# 01_MAIN.net
KiCad netlist of a schematic drawn in Altium Designer
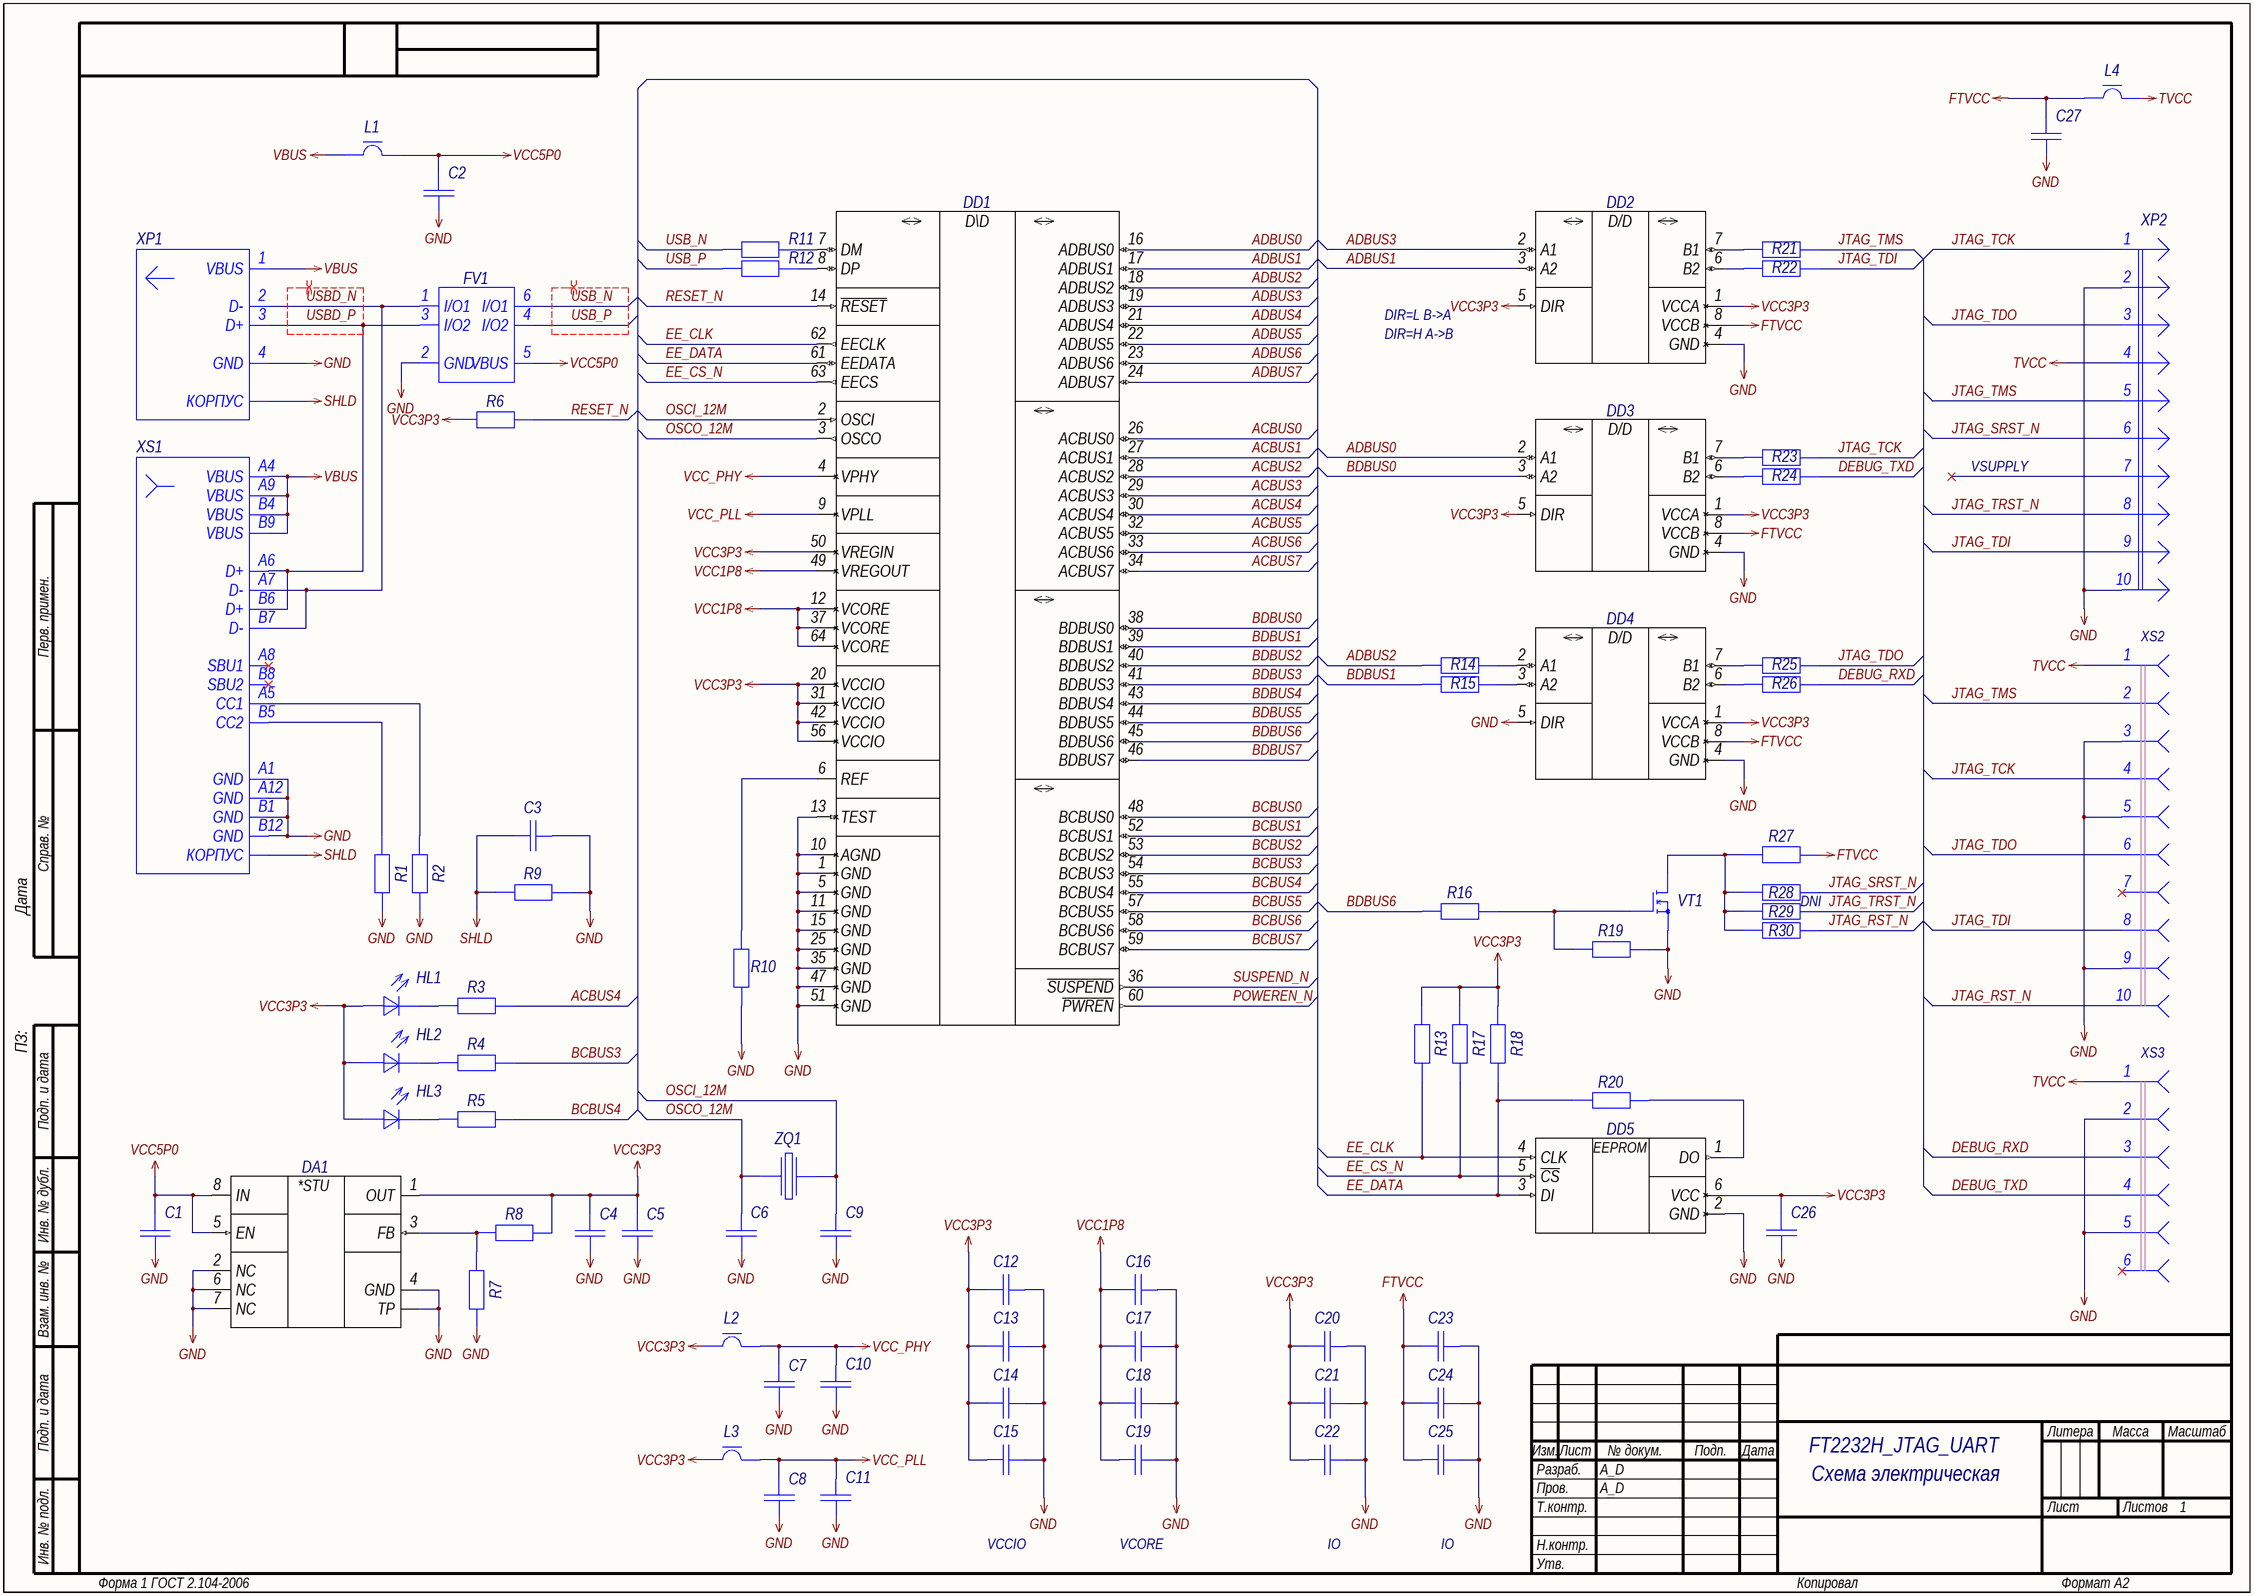
[diagram p0: 01_MAIN.SchDoc]

(export (version "E")
  (design (tool "Eeschema 10.0.6"))
  (components
    (comp (ref "C1")
      (value "Capacitor")
      (footprint "C0402_L")
      (fields
        (field (name "PART NUMBER") "GRM155R61C105KA12D")
        (field (name "VOLTAGE") "16V")
        (field (name "TOLERANCE") "±10%")
        (field (name "PUBLISHER") "Andrew Danich")
      )
      (libsource (lib "ADLib") (part "Capacitor"))
    )
    (comp (ref "C2")
      (value "Capacitor")
      (footprint "C0603_L")
      (fields
        (field (name "PART NUMBER") "GRM188R61A106KE69D")
        (field (name "VOLTAGE") "10V")
        (field (name "TOLERANCE") "±10%")
        (field (name "PUBLISHER") "Andrew Danich")
      )
      (libsource (lib "ADLib") (part "Capacitor"))
    )
    (comp (ref "C3")
      (value "~")
      (footprint "C0402_L")
      (fields
        (field (name "PART NUMBER") "GCM155R71C104KA55D")
        (field (name "VOLTAGE") "16V")
        (field (name "TOLERANCE") "±10%")
        (field (name "PUBLISHER") "Andrew Danich")
      )
      (libsource (lib "ADLib") (part "Capacitor"))
    )
    (comp (ref "C4")
      (value "Capacitor")
      (footprint "C0402_L")
      (fields
        (field (name "PART NUMBER") "GRM155R60J475ME87D")
        (field (name "VOLTAGE") "6.3V")
        (field (name "TOLERANCE") "±20%")
        (field (name "PUBLISHER") "Andrew Danich")
      )
      (libsource (lib "ADLib") (part "Capacitor"))
    )
    (comp (ref "C5")
      (value "Capacitor")
      (footprint "C0402_L")
      (fields
        (field (name "PART NUMBER") "GRM155R60J475ME87D")
        (field (name "VOLTAGE") "6.3V")
        (field (name "TOLERANCE") "±20%")
        (field (name "PUBLISHER") "Andrew Danich")
      )
      (libsource (lib "ADLib") (part "Capacitor"))
    )
    (comp (ref "C6")
      (value "Capacitor")
      (footprint "C0402_L")
      (fields
        (field (name "PART NUMBER") "GJM1555C1H120GB01D")
        (field (name "VOLTAGE") "50V")
        (field (name "TOLERANCE") "±2%")
        (field (name "PUBLISHER") "Andrew Danich")
      )
      (libsource (lib "ADLib") (part "Capacitor"))
    )
    (comp (ref "C7")
      (value "Capacitor")
      (footprint "C0402_L")
      (fields
        (field (name "PART NUMBER") "GRM155R60J475ME87D")
        (field (name "VOLTAGE") "6.3V")
        (field (name "TOLERANCE") "±20%")
        (field (name "PUBLISHER") "Andrew Danich")
      )
      (libsource (lib "ADLib") (part "Capacitor"))
    )
    (comp (ref "C8")
      (value "Capacitor")
      (footprint "C0402_L")
      (fields
        (field (name "PART NUMBER") "GRM155R60J475ME87D")
        (field (name "VOLTAGE") "6.3V")
        (field (name "TOLERANCE") "±20%")
        (field (name "PUBLISHER") "Andrew Danich")
      )
      (libsource (lib "ADLib") (part "Capacitor"))
    )
    (comp (ref "C9")
      (value "Capacitor")
      (footprint "C0402_L")
      (fields
        (field (name "PART NUMBER") "GJM1555C1H120GB01D")
        (field (name "VOLTAGE") "50V")
        (field (name "TOLERANCE") "±2%")
        (field (name "PUBLISHER") "Andrew Danich")
      )
      (libsource (lib "ADLib") (part "Capacitor"))
    )
    (comp (ref "C10")
      (value "Capacitor")
      (footprint "C0402_L")
      (fields
        (field (name "PART NUMBER") "GCM155R71C104KA55D")
        (field (name "VOLTAGE") "16V")
        (field (name "TOLERANCE") "±10%")
        (field (name "PUBLISHER") "Andrew Danich")
      )
      (libsource (lib "ADLib") (part "Capacitor"))
    )
    (comp (ref "C11")
      (value "Capacitor")
      (footprint "C0402_L")
      (fields
        (field (name "PART NUMBER") "GCM155R71C104KA55D")
        (field (name "VOLTAGE") "16V")
        (field (name "TOLERANCE") "±10%")
        (field (name "PUBLISHER") "Andrew Danich")
      )
      (libsource (lib "ADLib") (part "Capacitor"))
    )
    (comp (ref "C12")
      (value "Capacitor")
      (footprint "C0402_L")
      (fields
        (field (name "PART NUMBER") "GCM155R71C104KA55D")
        (field (name "VOLTAGE") "16V")
        (field (name "TOLERANCE") "±10%")
        (field (name "PUBLISHER") "Andrew Danich")
      )
      (libsource (lib "ADLib") (part "Capacitor"))
    )
    (comp (ref "C13")
      (value "Capacitor")
      (footprint "C0402_L")
      (fields
        (field (name "PART NUMBER") "GCM155R71C104KA55D")
        (field (name "VOLTAGE") "16V")
        (field (name "TOLERANCE") "±10%")
        (field (name "PUBLISHER") "Andrew Danich")
      )
      (libsource (lib "ADLib") (part "Capacitor"))
    )
    (comp (ref "C14")
      (value "Capacitor")
      (footprint "C0402_L")
      (fields
        (field (name "PART NUMBER") "GCM155R71C104KA55D")
        (field (name "VOLTAGE") "16V")
        (field (name "TOLERANCE") "±10%")
        (field (name "PUBLISHER") "Andrew Danich")
      )
      (libsource (lib "ADLib") (part "Capacitor"))
    )
    (comp (ref "C15")
      (value "Capacitor")
      (footprint "C0402_L")
      (fields
        (field (name "PART NUMBER") "GCM155R71C104KA55D")
        (field (name "VOLTAGE") "16V")
        (field (name "TOLERANCE") "±10%")
        (field (name "PUBLISHER") "Andrew Danich")
      )
      (libsource (lib "ADLib") (part "Capacitor"))
    )
    (comp (ref "C16")
      (value "Capacitor")
      (footprint "C0402_L")
      (fields
        (field (name "PART NUMBER") "GRM155R60J475ME87D")
        (field (name "VOLTAGE") "6.3V")
        (field (name "TOLERANCE") "±20%")
        (field (name "PUBLISHER") "Andrew Danich")
      )
      (libsource (lib "ADLib") (part "Capacitor"))
    )
    (comp (ref "C17")
      (value "Capacitor")
      (footprint "C0402_L")
      (fields
        (field (name "PART NUMBER") "GCM155R71C104KA55D")
        (field (name "VOLTAGE") "16V")
        (field (name "TOLERANCE") "±10%")
        (field (name "PUBLISHER") "Andrew Danich")
      )
      (libsource (lib "ADLib") (part "Capacitor"))
    )
    (comp (ref "C18")
      (value "Capacitor")
      (footprint "C0402_L")
      (fields
        (field (name "PART NUMBER") "GCM155R71C104KA55D")
        (field (name "VOLTAGE") "16V")
        (field (name "TOLERANCE") "±10%")
        (field (name "PUBLISHER") "Andrew Danich")
      )
      (libsource (lib "ADLib") (part "Capacitor"))
    )
    (comp (ref "C19")
      (value "Capacitor")
      (footprint "C0402_L")
      (fields
        (field (name "PART NUMBER") "GCM155R71C104KA55D")
        (field (name "VOLTAGE") "16V")
        (field (name "TOLERANCE") "±10%")
        (field (name "PUBLISHER") "Andrew Danich")
      )
      (libsource (lib "ADLib") (part "Capacitor"))
    )
    (comp (ref "C20")
      (value "Capacitor")
      (footprint "C0402_L")
      (fields
        (field (name "PART NUMBER") "GCM155R71C104KA55D")
        (field (name "VOLTAGE") "16V")
        (field (name "TOLERANCE") "±10%")
        (field (name "PUBLISHER") "Andrew Danich")
      )
      (libsource (lib "ADLib") (part "Capacitor"))
    )
    (comp (ref "C21")
      (value "Capacitor")
      (footprint "C0402_L")
      (fields
        (field (name "PART NUMBER") "GCM155R71C104KA55D")
        (field (name "VOLTAGE") "16V")
        (field (name "TOLERANCE") "±10%")
        (field (name "PUBLISHER") "Andrew Danich")
      )
      (libsource (lib "ADLib") (part "Capacitor"))
    )
    (comp (ref "C22")
      (value "Capacitor")
      (footprint "C0402_L")
      (fields
        (field (name "PART NUMBER") "GCM155R71C104KA55D")
        (field (name "VOLTAGE") "16V")
        (field (name "TOLERANCE") "±10%")
        (field (name "PUBLISHER") "Andrew Danich")
      )
      (libsource (lib "ADLib") (part "Capacitor"))
    )
    (comp (ref "C23")
      (value "Capacitor")
      (footprint "C0402_L")
      (fields
        (field (name "PART NUMBER") "GCM155R71C104KA55D")
        (field (name "VOLTAGE") "16V")
        (field (name "TOLERANCE") "±10%")
        (field (name "PUBLISHER") "Andrew Danich")
      )
      (libsource (lib "ADLib") (part "Capacitor"))
    )
    (comp (ref "C24")
      (value "Capacitor")
      (footprint "C0402_L")
      (fields
        (field (name "PART NUMBER") "GCM155R71C104KA55D")
        (field (name "VOLTAGE") "16V")
        (field (name "TOLERANCE") "±10%")
        (field (name "PUBLISHER") "Andrew Danich")
      )
      (libsource (lib "ADLib") (part "Capacitor"))
    )
    (comp (ref "C25")
      (value "Capacitor")
      (footprint "C0402_L")
      (fields
        (field (name "PART NUMBER") "GCM155R71C104KA55D")
        (field (name "VOLTAGE") "16V")
        (field (name "TOLERANCE") "±10%")
        (field (name "PUBLISHER") "Andrew Danich")
      )
      (libsource (lib "ADLib") (part "Capacitor"))
    )
    (comp (ref "C26")
      (value "Capacitor")
      (footprint "C0402_L")
      (fields
        (field (name "PART NUMBER") "GCM155R71C104KA55D")
        (field (name "VOLTAGE") "16V")
        (field (name "TOLERANCE") "±10%")
        (field (name "PUBLISHER") "Andrew Danich")
      )
      (libsource (lib "ADLib") (part "Capacitor"))
    )
    (comp (ref "C27")
      (value "Capacitor")
      (footprint "C0402_L")
      (fields
        (field (name "PART NUMBER") "GRM155D71C225ME11D")
        (field (name "VOLTAGE") "16V")
        (field (name "TOLERANCE") "±20%")
        (field (name "PUBLISHER") "Andrew Danich")
      )
      (libsource (lib "ADLib") (part "Capacitor"))
    )
    (comp (ref "DA1")
      (value "TPS73701DRB")
      (footprint "VSON-8_065P300X300X100_N")
      (fields
        (field (name "PART NUMBER") "TPS73701DRBR")
        (field (name "MANUFACTURER") "Texas Instruments")
        (field (name "PUBLISHER") "Andrew Danich")
      )
      (libsource (lib "ADLib") (part "TPS73701DRB"))
    )
    (comp (ref "DD1")
      (value "FT2232Hx-Series")
      (footprint "LQFP-64_050P1000X1000X160_N")
      (fields
        (field (name "PART NUMBER") "FT2232HL")
        (field (name "MANUFACTURER") "FTDI")
        (field (name "PUBLISHER") "Andrew Danich")
      )
      (libsource (lib "ADLib") (part "FT2232Hx-Series"))
    )
    (comp (ref "DD2")
      (value "SN74LVC2T45DCx-Series")
      (footprint "VSSOP-8_050P200X230X090_N")
      (fields
        (field (name "PART NUMBER") "SN74LVC2T45DCUR")
        (field (name "MANUFACTURER") "Texas Instruments")
        (field (name "PUBLISHER") "Andrew Danich")
      )
      (libsource (lib "ADLib") (part "SN74LVC2T45DCx-Series"))
    )
    (comp (ref "DD3")
      (value "SN74LVC2T45DCx-Series")
      (footprint "VSSOP-8_050P200X230X090_N")
      (fields
        (field (name "PART NUMBER") "SN74LVC2T45DCUR")
        (field (name "MANUFACTURER") "Texas Instruments")
        (field (name "PUBLISHER") "Andrew Danich")
      )
      (libsource (lib "ADLib") (part "SN74LVC2T45DCx-Series"))
    )
    (comp (ref "DD4")
      (value "SN74LVC2T45DCx-Series")
      (footprint "VSSOP-8_050P200X230X090_N")
      (fields
        (field (name "PART NUMBER") "SN74LVC2T45DCUR")
        (field (name "MANUFACTURER") "Texas Instruments")
        (field (name "PUBLISHER") "Andrew Danich")
      )
      (libsource (lib "ADLib") (part "SN74LVC2T45DCx-Series"))
    )
    (comp (ref "DD5")
      (value "93xx56xx-OT-Series")
      (footprint "SOT-23-6_095P290X160X145_N")
      (fields
        (field (name "PART NUMBER") "93LC56BT-I/OT")
        (field (name "MANUFACTURER") "Microchip")
        (field (name "PUBLISHER") "Andrew Danich")
      )
      (libsource (lib "ADLib") (part "93xx56xx-OT-Series"))
    )
    (comp (ref "FV1")
      (value "USBLC6-2x6")
      (footprint "SOT-666_050P160X120X060_N")
      (fields
        (field (name "PART NUMBER") "USBLC6-2P6")
        (field (name "MANUFACTURER") "STMicroelectronics")
        (field (name "PUBLISHER") "Andrew Danich")
      )
      (libsource (lib "ADLib") (part "USBLC6-2x6"))
    )
    (comp (ref "HL1")
      (value "Text")
      (footprint "LD0402")
      (fields
        (field (name "PART NUMBER") "KPHHS-1005QBC-D-V")
        (field (name "MANUFACTURER") "Kingbright")
        (field (name "PUBLISHER") "Andrew Danich")
      )
      (libsource (lib "ADLib") (part "Led-1"))
    )
    (comp (ref "HL2")
      (value "Text")
      (footprint "LD0402")
      (fields
        (field (name "PART NUMBER") "KPHHS-1005QBC-D-V")
        (field (name "MANUFACTURER") "Kingbright")
        (field (name "PUBLISHER") "Andrew Danich")
      )
      (libsource (lib "ADLib") (part "Led-1"))
    )
    (comp (ref "HL3")
      (value "Text")
      (footprint "LD0402")
      (fields
        (field (name "PART NUMBER") "KPHHS-1005QBC-D-V")
        (field (name "MANUFACTURER") "Kingbright")
        (field (name "PUBLISHER") "Andrew Danich")
      )
      (libsource (lib "ADLib") (part "Led-1"))
    )
    (comp (ref "L1")
      (value "FerriteBead")
      (footprint "L0402_L")
      (fields
        (field (name "PART NUMBER") "BLM15PD121SN1D")
        (field (name "TOLERANCE") "±25%")
        (field (name "MANUFACTURER") "Murata")
        (field (name "PUBLISHER") "Andrew Danich")
      )
      (libsource (lib "ADLib") (part "FerriteBead"))
    )
    (comp (ref "L2")
      (value "FerriteBead")
      (footprint "L0402_L")
      (fields
        (field (name "PART NUMBER") "BLM15PD121SN1D")
        (field (name "TOLERANCE") "±25%")
        (field (name "MANUFACTURER") "Murata")
        (field (name "PUBLISHER") "Andrew Danich")
      )
      (libsource (lib "ADLib") (part "FerriteBead"))
    )
    (comp (ref "L3")
      (value "FerriteBead")
      (footprint "L0402_L")
      (fields
        (field (name "PART NUMBER") "BLM15PD121SN1D")
        (field (name "TOLERANCE") "±25%")
        (field (name "MANUFACTURER") "Murata")
        (field (name "PUBLISHER") "Andrew Danich")
      )
      (libsource (lib "ADLib") (part "FerriteBead"))
    )
    (comp (ref "L4")
      (value "FerriteBead")
      (footprint "L0402_L")
      (fields
        (field (name "PART NUMBER") "BLM15PD121SN1D")
        (field (name "TOLERANCE") "±25%")
        (field (name "MANUFACTURER") "Murata")
        (field (name "PUBLISHER") "Andrew Danich")
      )
      (libsource (lib "ADLib") (part "FerriteBead"))
    )
    (comp (ref "R1")
      (value "Resistor")
      (footprint "R0402_L")
      (fields
        (field (name "PART NUMBER") "RC0402FR-075K1L")
        (field (name "TOLERANCE") "±1%")
        (field (name "MANUFACTURER") "Yageo")
        (field (name "PUBLISHER") "Andrew Danich")
      )
      (libsource (lib "ADLib") (part "Resistor"))
    )
    (comp (ref "R2")
      (value "Resistor")
      (footprint "R0402_L")
      (fields
        (field (name "PART NUMBER") "RC0402FR-075K1L")
        (field (name "TOLERANCE") "±1%")
        (field (name "MANUFACTURER") "Yageo")
        (field (name "PUBLISHER") "Andrew Danich")
      )
      (libsource (lib "ADLib") (part "Resistor"))
    )
    (comp (ref "R3")
      (value "Resistor")
      (footprint "R0402_L")
      (fields
        (field (name "PART NUMBER") "RC0402JR-071KL")
        (field (name "TOLERANCE") "±5%")
        (field (name "MANUFACTURER") "Yageo")
        (field (name "PUBLISHER") "Andrew Danich")
      )
      (libsource (lib "ADLib") (part "Resistor"))
    )
    (comp (ref "R4")
      (value "Resistor")
      (footprint "R0402_L")
      (fields
        (field (name "PART NUMBER") "RC0402JR-071KL")
        (field (name "TOLERANCE") "±5%")
        (field (name "MANUFACTURER") "Yageo")
        (field (name "PUBLISHER") "Andrew Danich")
      )
      (libsource (lib "ADLib") (part "Resistor"))
    )
    (comp (ref "R5")
      (value "Resistor")
      (footprint "R0402_L")
      (fields
        (field (name "PART NUMBER") "RC0402JR-071KL")
        (field (name "TOLERANCE") "±5%")
        (field (name "MANUFACTURER") "Yageo")
        (field (name "PUBLISHER") "Andrew Danich")
      )
      (libsource (lib "ADLib") (part "Resistor"))
    )
    (comp (ref "R6")
      (value "Resistor")
      (footprint "R0402_L")
      (fields
        (field (name "PART NUMBER") "RC0402JR-071KL")
        (field (name "TOLERANCE") "±5%")
        (field (name "MANUFACTURER") "Yageo")
        (field (name "PUBLISHER") "Andrew Danich")
      )
      (libsource (lib "ADLib") (part "Resistor"))
    )
    (comp (ref "R7")
      (value "Resistor")
      (footprint "R0402_L")
      (fields
        (field (name "PART NUMBER") "RC0402FR-0712KL")
        (field (name "TOLERANCE") "±1%")
        (field (name "MANUFACTURER") "Yageo")
        (field (name "PUBLISHER") "Andrew Danich")
      )
      (libsource (lib "ADLib") (part "Resistor"))
    )
    (comp (ref "R8")
      (value "Resistor")
      (footprint "R0402_L")
      (fields
        (field (name "PART NUMBER") "RC0402FR-0722K1L")
        (field (name "TOLERANCE") "±1%")
        (field (name "MANUFACTURER") "Yageo")
        (field (name "PUBLISHER") "Andrew Danich")
      )
      (libsource (lib "ADLib") (part "Resistor"))
    )
    (comp (ref "R9")
      (value "~")
      (footprint "R0402_L")
      (fields
        (field (name "PART NUMBER") "RC0402JR-07100KL")
        (field (name "TOLERANCE") "±5%")
        (field (name "MANUFACTURER") "Yageo")
        (field (name "PUBLISHER") "Andrew Danich")
      )
      (libsource (lib "ADLib") (part "Resistor"))
    )
    (comp (ref "R10")
      (value "Resistor")
      (footprint "R0402_L")
      (fields
        (field (name "PART NUMBER") "RC0402FR-0712KL")
        (field (name "TOLERANCE") "±1%")
        (field (name "MANUFACTURER") "Yageo")
        (field (name "PUBLISHER") "Andrew Danich")
      )
      (libsource (lib "ADLib") (part "Resistor"))
    )
    (comp (ref "R11")
      (value "Resistor")
      (footprint "R0402_L")
      (fields
        (field (name "PART NUMBER") "RC0402JR-0710RL")
        (field (name "TOLERANCE") "±5%")
        (field (name "MANUFACTURER") "Yageo")
        (field (name "PUBLISHER") "Andrew Danich")
      )
      (libsource (lib "ADLib") (part "Resistor"))
    )
    (comp (ref "R12")
      (value "Resistor")
      (footprint "R0402_L")
      (fields
        (field (name "PART NUMBER") "RC0402JR-0710RL")
        (field (name "TOLERANCE") "±5%")
        (field (name "MANUFACTURER") "Yageo")
        (field (name "PUBLISHER") "Andrew Danich")
      )
      (libsource (lib "ADLib") (part "Resistor"))
    )
    (comp (ref "R13")
      (value "Resistor")
      (footprint "R0402_L")
      (fields
        (field (name "PART NUMBER") "RC0402JR-0710KL")
        (field (name "TOLERANCE") "±5%")
        (field (name "MANUFACTURER") "Yageo")
        (field (name "PUBLISHER") "Andrew Danich")
      )
      (libsource (lib "ADLib") (part "Resistor"))
    )
    (comp (ref "R14")
      (value "Resistor")
      (footprint "R0402_L")
      (fields
        (field (name "PART NUMBER") "RC0402JR-07100RL")
        (field (name "TOLERANCE") "±5%")
        (field (name "MANUFACTURER") "Yageo")
        (field (name "PUBLISHER") "Andrew Danich")
      )
      (libsource (lib "ADLib") (part "Resistor"))
    )
    (comp (ref "R15")
      (value "Resistor")
      (footprint "R0402_L")
      (fields
        (field (name "PART NUMBER") "RC0402JR-07100RL")
        (field (name "TOLERANCE") "±5%")
        (field (name "MANUFACTURER") "Yageo")
        (field (name "PUBLISHER") "Andrew Danich")
      )
      (libsource (lib "ADLib") (part "Resistor"))
    )
    (comp (ref "R16")
      (value "Resistor")
      (footprint "R0402_L")
      (fields
        (field (name "PART NUMBER") "RC0402JR-07100RL")
        (field (name "TOLERANCE") "±5%")
        (field (name "MANUFACTURER") "Yageo")
        (field (name "PUBLISHER") "Andrew Danich")
      )
      (libsource (lib "ADLib") (part "Resistor"))
    )
    (comp (ref "R17")
      (value "Resistor")
      (footprint "R0402_L")
      (fields
        (field (name "PART NUMBER") "RC0402JR-0710KL")
        (field (name "TOLERANCE") "±5%")
        (field (name "MANUFACTURER") "Yageo")
        (field (name "PUBLISHER") "Andrew Danich")
      )
      (libsource (lib "ADLib") (part "Resistor"))
    )
    (comp (ref "R18")
      (value "Resistor")
      (footprint "R0402_L")
      (fields
        (field (name "PART NUMBER") "RC0402JR-0710KL")
        (field (name "TOLERANCE") "±5%")
        (field (name "MANUFACTURER") "Yageo")
        (field (name "PUBLISHER") "Andrew Danich")
      )
      (libsource (lib "ADLib") (part "Resistor"))
    )
    (comp (ref "R19")
      (value "Resistor")
      (footprint "R0402_L")
      (fields
        (field (name "PART NUMBER") "RC0402JR-0710KL")
        (field (name "TOLERANCE") "±5%")
        (field (name "MANUFACTURER") "Yageo")
        (field (name "PUBLISHER") "Andrew Danich")
      )
      (libsource (lib "ADLib") (part "Resistor"))
    )
    (comp (ref "R20")
      (value "Resistor")
      (footprint "R0402_L")
      (fields
        (field (name "PART NUMBER") "RC0402JR-072K2L")
        (field (name "TOLERANCE") "±5%")
        (field (name "MANUFACTURER") "Yageo")
        (field (name "PUBLISHER") "Andrew Danich")
      )
      (libsource (lib "ADLib") (part "Resistor"))
    )
    (comp (ref "R21")
      (value "Resistor")
      (footprint "R0402_L")
      (fields
        (field (name "PART NUMBER") "RC0402JR-07100RL")
        (field (name "TOLERANCE") "±5%")
        (field (name "MANUFACTURER") "Yageo")
        (field (name "PUBLISHER") "Andrew Danich")
      )
      (libsource (lib "ADLib") (part "Resistor"))
    )
    (comp (ref "R22")
      (value "Resistor")
      (footprint "R0402_L")
      (fields
        (field (name "PART NUMBER") "RC0402JR-07100RL")
        (field (name "TOLERANCE") "±5%")
        (field (name "MANUFACTURER") "Yageo")
        (field (name "PUBLISHER") "Andrew Danich")
      )
      (libsource (lib "ADLib") (part "Resistor"))
    )
    (comp (ref "R23")
      (value "Resistor")
      (footprint "R0402_L")
      (fields
        (field (name "PART NUMBER") "RC0402JR-07100RL")
        (field (name "TOLERANCE") "±5%")
        (field (name "MANUFACTURER") "Yageo")
        (field (name "PUBLISHER") "Andrew Danich")
      )
      (libsource (lib "ADLib") (part "Resistor"))
    )
    (comp (ref "R24")
      (value "Resistor")
      (footprint "R0402_L")
      (fields
        (field (name "PART NUMBER") "RC0402JR-07100RL")
        (field (name "TOLERANCE") "±5%")
        (field (name "MANUFACTURER") "Yageo")
        (field (name "PUBLISHER") "Andrew Danich")
      )
      (libsource (lib "ADLib") (part "Resistor"))
    )
    (comp (ref "R25")
      (value "Resistor")
      (footprint "R0402_L")
      (fields
        (field (name "PART NUMBER") "RC0402JR-07100RL")
        (field (name "TOLERANCE") "±5%")
        (field (name "MANUFACTURER") "Yageo")
        (field (name "PUBLISHER") "Andrew Danich")
      )
      (libsource (lib "ADLib") (part "Resistor"))
    )
    (comp (ref "R26")
      (value "Resistor")
      (footprint "R0402_L")
      (fields
        (field (name "PART NUMBER") "RC0402JR-07100RL")
        (field (name "TOLERANCE") "±5%")
        (field (name "MANUFACTURER") "Yageo")
        (field (name "PUBLISHER") "Andrew Danich")
      )
      (libsource (lib "ADLib") (part "Resistor"))
    )
    (comp (ref "R27")
      (value "Resistor")
      (footprint "R0402_L")
      (fields
        (field (name "PART NUMBER") "RC0402JR-0710KL")
        (field (name "TOLERANCE") "±5%")
        (field (name "MANUFACTURER") "Yageo")
        (field (name "PUBLISHER") "Andrew Danich")
      )
      (libsource (lib "ADLib") (part "Resistor"))
    )
    (comp (ref "R28")
      (value "Resistor")
      (footprint "R0402_L")
      (fields
        (field (name "PART NUMBER") "RC0402JR-070RL")
        (field (name "TOLERANCE") "±5%")
        (field (name "MANUFACTURER") "Yageo")
        (field (name "PUBLISHER") "Andrew Danich")
      )
      (libsource (lib "ADLib") (part "Resistor"))
    )
    (comp (ref "R29")
      (value "Resistor")
      (footprint "R0402_L")
      (fields
        (field (name "PART NUMBER") "RC0402JR-070RL")
        (field (name "TOLERANCE") "±5%")
        (field (name "MANUFACTURER") "Yageo")
        (field (name "PUBLISHER") "Andrew Danich")
      )
      (libsource (lib "ADLib") (part "Resistor"))
    )
    (comp (ref "R30")
      (value "Resistor")
      (footprint "R0402_L")
      (fields
        (field (name "PART NUMBER") "RC0402JR-070RL")
        (field (name "TOLERANCE") "±5%")
        (field (name "MANUFACTURER") "Yageo")
        (field (name "PUBLISHER") "Andrew Danich")
      )
      (libsource (lib "ADLib") (part "Resistor"))
    )
    (comp (ref "VT1")
      (value "MOSFET-N_32")
      (footprint "SOT-883B_035P060X100X040_N")
      (fields
        (field (name "PART NUMBER") "NX3008NBKMB")
        (field (name "MANUFACTURER") "NXP Semiconductors")
        (field (name "PUBLISHER") "Andrew Danich")
      )
      (libsource (lib "ADLib") (part "MOSFET-N_32"))
    )
    (comp (ref "XP1")
      (value "Text")
      (footprint "DS1097")
      (fields
        (field (name "PART NUMBER") "DS1097-B")
        (field (name "MANUFACTURER") "Connfly Electronic Co., Ltd")
        (field (name "PUBLISHER") "Andrew Danich")
      )
      (libsource (lib "ADLib") (part "Con-5-M-USB"))
    )
    (comp (ref "XP2")
      (value "JTAG")
      (footprint "IDC-10MR")
      (fields (field (name "PART NUMBER") "IDC-10MR") (field (name "PUBLISHER") "Andrew Danich"))
      (libsource (lib "ADLib") (part "Con-10-M"))
    )
    (comp (ref "XS1")
      (value "Text")
      (footprint "U262-161N-4BVC11")
      (fields
        (field (name "PART NUMBER") "U262-161N-4BVC11")
        (field (name "MANUFACTURER") "XKB Enterprise")
        (field (name "PUBLISHER") "Andrew Danich")
      )
      (libsource (lib "ADLib") (part "Con-USB_C-F-16P"))
    )
    (comp (ref "XS2")
      (value "JTAG-FFC")
      (footprint "XF2M-1015-1A")
      (fields
        (field (name "PART NUMBER") "XF2M-1015-1A")
        (field (name "MANUFACTURER") "Omron Electronics")
        (field (name "PUBLISHER") "Viktor Klishin")
      )
      (libsource (lib "ADLib") (part "Con-10-F_S"))
    )
    (comp (ref "XS3")
      (value "SWO")
      (footprint "XF2M-0615-1A")
      (fields
        (field (name "PART NUMBER") "XF2M-0615-1A")
        (field (name "MANUFACTURER") "Omron Electronics")
        (field (name "PUBLISHER") "Viktor Klishin")
      )
      (libsource (lib "ADLib") (part "Con-6-F_S"))
    )
    (comp (ref "ZQ1")
      (value "Crystal-1_3p")
      (footprint "SMD 3.2x2.5mm")
      (fields
        (field (name "PART NUMBER") "12.88673_KX-7T-12.0MHz")
        (field (name "MANUFACTURER") "GEYER ELECTRONIC")
        (field (name "PUBLISHER") "Andrew Danich")
      )
      (libsource (lib "ADLib") (part "Crystal-1_3p"))
    )
  )
  (nets
    (net (code "1") (name "/ACBUS0") (class "Default")
      (node (ref "DD1") (pin "26") (pinfunction "ACBUS0_26") (pintype "bidirectional"))
    )
    (net (code "2") (name "/ACBUS1") (class "Default")
      (node (ref "DD1") (pin "27") (pinfunction "ACBUS1_27") (pintype "bidirectional"))
    )
    (net (code "3") (name "/ACBUS2") (class "Default")
      (node (ref "DD1") (pin "28") (pinfunction "ACBUS2_28") (pintype "bidirectional"))
    )
    (net (code "4") (name "/ACBUS3") (class "Default")
      (node (ref "DD1") (pin "29") (pinfunction "ACBUS3_29") (pintype "bidirectional"))
    )
    (net (code "5") (name "/ACBUS4") (class "Default")
      (node (ref "DD1") (pin "30") (pinfunction "ACBUS4_30") (pintype "bidirectional"))
      (node (ref "R3") (pin "2") (pinfunction "2_2") (pintype "passive"))
    )
    (net (code "6") (name "/ACBUS5") (class "Default")
      (node (ref "DD1") (pin "32") (pinfunction "ACBUS5_32") (pintype "bidirectional"))
    )
    (net (code "7") (name "/ACBUS6") (class "Default")
      (node (ref "DD1") (pin "33") (pinfunction "ACBUS6_33") (pintype "bidirectional"))
    )
    (net (code "8") (name "/ACBUS7") (class "Default")
      (node (ref "DD1") (pin "34") (pinfunction "ACBUS7_34") (pintype "bidirectional"))
    )
    (net (code "9") (name "/ADBUS0") (class "Default")
      (node (ref "DD1") (pin "16") (pinfunction "ADBUS0_16") (pintype "bidirectional"))
      (node (ref "DD3") (pin "2") (pinfunction "A1_2") (pintype "bidirectional"))
    )
    (net (code "10") (name "/ADBUS1") (class "Default")
      (node (ref "DD1") (pin "17") (pinfunction "ADBUS1_17") (pintype "bidirectional"))
      (node (ref "DD2") (pin "3") (pinfunction "A2_3") (pintype "bidirectional"))
    )
    (net (code "11") (name "/ADBUS2") (class "Default")
      (node (ref "DD1") (pin "18") (pinfunction "ADBUS2_18") (pintype "bidirectional"))
      (node (ref "R14") (pin "1") (pinfunction "1_1") (pintype "passive"))
    )
    (net (code "12") (name "/ADBUS3") (class "Default")
      (node (ref "DD1") (pin "19") (pinfunction "ADBUS3_19") (pintype "bidirectional"))
      (node (ref "DD2") (pin "2") (pinfunction "A1_2") (pintype "bidirectional"))
    )
    (net (code "13") (name "/ADBUS4") (class "Default")
      (node (ref "DD1") (pin "21") (pinfunction "ADBUS4_21") (pintype "bidirectional"))
    )
    (net (code "14") (name "/ADBUS5") (class "Default")
      (node (ref "DD1") (pin "22") (pinfunction "ADBUS5_22") (pintype "bidirectional"))
    )
    (net (code "15") (name "/ADBUS6") (class "Default")
      (node (ref "DD1") (pin "23") (pinfunction "ADBUS6_23") (pintype "bidirectional"))
    )
    (net (code "16") (name "/ADBUS7") (class "Default")
      (node (ref "DD1") (pin "24") (pinfunction "ADBUS7_24") (pintype "bidirectional"))
    )
    (net (code "17") (name "/BCBUS0") (class "Default")
      (node (ref "DD1") (pin "48") (pinfunction "BCBUS0_48") (pintype "bidirectional"))
    )
    (net (code "18") (name "/BCBUS1") (class "Default")
      (node (ref "DD1") (pin "52") (pinfunction "BCBUS1_52") (pintype "bidirectional"))
    )
    (net (code "19") (name "/BCBUS2") (class "Default")
      (node (ref "DD1") (pin "53") (pinfunction "BCBUS2_53") (pintype "bidirectional"))
    )
    (net (code "20") (name "/BCBUS3") (class "Default")
      (node (ref "DD1") (pin "54") (pinfunction "BCBUS3_54") (pintype "bidirectional"))
      (node (ref "R4") (pin "2") (pinfunction "2_2") (pintype "passive"))
    )
    (net (code "21") (name "/BCBUS4") (class "Default")
      (node (ref "DD1") (pin "55") (pinfunction "BCBUS4_55") (pintype "bidirectional"))
      (node (ref "R5") (pin "2") (pinfunction "2_2") (pintype "passive"))
    )
    (net (code "22") (name "/BCBUS5") (class "Default")
      (node (ref "DD1") (pin "57") (pinfunction "BCBUS5_57") (pintype "bidirectional"))
    )
    (net (code "23") (name "/BCBUS6") (class "Default")
      (node (ref "DD1") (pin "58") (pinfunction "BCBUS6_58") (pintype "bidirectional"))
    )
    (net (code "24") (name "/BCBUS7") (class "Default")
      (node (ref "DD1") (pin "59") (pinfunction "BCBUS7_59") (pintype "bidirectional"))
    )
    (net (code "25") (name "/BDBUS0") (class "Default")
      (node (ref "DD1") (pin "38") (pinfunction "BDBUS0_38") (pintype "bidirectional"))
      (node (ref "DD3") (pin "3") (pinfunction "A2_3") (pintype "bidirectional"))
    )
    (net (code "26") (name "/BDBUS1") (class "Default")
      (node (ref "DD1") (pin "39") (pinfunction "BDBUS1_39") (pintype "bidirectional"))
      (node (ref "R15") (pin "1") (pinfunction "1_1") (pintype "passive"))
    )
    (net (code "27") (name "/BDBUS2") (class "Default")
      (node (ref "DD1") (pin "40") (pinfunction "BDBUS2_40") (pintype "bidirectional"))
    )
    (net (code "28") (name "/BDBUS3") (class "Default")
      (node (ref "DD1") (pin "41") (pinfunction "BDBUS3_41") (pintype "bidirectional"))
    )
    (net (code "29") (name "/BDBUS4") (class "Default")
      (node (ref "DD1") (pin "43") (pinfunction "BDBUS4_43") (pintype "bidirectional"))
    )
    (net (code "30") (name "/BDBUS5") (class "Default")
      (node (ref "DD1") (pin "44") (pinfunction "BDBUS5_44") (pintype "bidirectional"))
    )
    (net (code "31") (name "/BDBUS6") (class "Default")
      (node (ref "DD1") (pin "45") (pinfunction "BDBUS6_45") (pintype "bidirectional"))
      (node (ref "R16") (pin "1") (pinfunction "1_1") (pintype "passive"))
    )
    (net (code "32") (name "/BDBUS7") (class "Default")
      (node (ref "DD1") (pin "46") (pinfunction "BDBUS7_46") (pintype "bidirectional"))
    )
    (net (code "33") (name "/DEBUG_RXD") (class "Default")
      (node (ref "R26") (pin "2") (pinfunction "2_2") (pintype "passive"))
      (node (ref "XS3") (pin "3") (pintype "passive"))
    )
    (net (code "34") (name "/DEBUG_TXD") (class "Default")
      (node (ref "R24") (pin "2") (pinfunction "2_2") (pintype "passive"))
      (node (ref "XS3") (pin "4") (pintype "passive"))
    )
    (net (code "35") (name "/EE_CLK") (class "Default")
      (node (ref "DD1") (pin "62") (pinfunction "EECLK_62") (pintype "output"))
      (node (ref "DD5") (pin "4") (pinfunction "CLK_4") (pintype "input"))
      (node (ref "R13") (pin "1") (pinfunction "1_1") (pintype "passive"))
    )
    (net (code "36") (name "/EE_CS_N") (class "Default")
      (node (ref "DD1") (pin "63") (pinfunction "EECS_63") (pintype "output"))
      (node (ref "DD5") (pin "5") (pinfunction "~{CS}_5") (pintype "input"))
      (node (ref "R17") (pin "1") (pinfunction "1_1") (pintype "passive"))
    )
    (net (code "37") (name "/EE_DATA") (class "Default")
      (node (ref "DD1") (pin "61") (pinfunction "EEDATA_61") (pintype "bidirectional"))
      (node (ref "DD5") (pin "3") (pinfunction "DI_3") (pintype "input"))
      (node (ref "R18") (pin "1") (pinfunction "1_1") (pintype "passive"))
      (node (ref "R20") (pin "1") (pinfunction "1_1") (pintype "passive"))
    )
    (net (code "38") (name "/JTAG_RST_N") (class "Default")
      (node (ref "R30") (pin "2") (pinfunction "2_2") (pintype "passive"))
      (node (ref "XS2") (pin "10") (pintype "passive"))
    )
    (net (code "39") (name "/JTAG_SRST_N") (class "Default")
      (node (ref "R28") (pin "2") (pinfunction "2_2") (pintype "passive"))
      (node (ref "XP2") (pin "6") (pintype "passive"))
    )
    (net (code "40") (name "/JTAG_TCK") (class "Default")
      (node (ref "R23") (pin "2") (pinfunction "2_2") (pintype "passive"))
      (node (ref "XP2") (pin "1") (pintype "passive"))
      (node (ref "XS2") (pin "4") (pintype "passive"))
    )
    (net (code "41") (name "/JTAG_TDI") (class "Default")
      (node (ref "R22") (pin "2") (pinfunction "2_2") (pintype "passive"))
      (node (ref "XP2") (pin "9") (pintype "passive"))
      (node (ref "XS2") (pin "8") (pintype "passive"))
    )
    (net (code "42") (name "/JTAG_TDO") (class "Default")
      (node (ref "R25") (pin "2") (pinfunction "2_2") (pintype "passive"))
      (node (ref "XP2") (pin "3") (pintype "passive"))
      (node (ref "XS2") (pin "6") (pintype "passive"))
    )
    (net (code "43") (name "/JTAG_TMS") (class "Default")
      (node (ref "R21") (pin "2") (pinfunction "2_2") (pintype "passive"))
      (node (ref "XP2") (pin "5") (pintype "passive"))
      (node (ref "XS2") (pin "2") (pintype "passive"))
    )
    (net (code "44") (name "/JTAG_TRST_N") (class "Default")
      (node (ref "R29") (pin "2") (pinfunction "2_2") (pintype "passive"))
      (node (ref "XP2") (pin "8") (pintype "passive"))
    )
    (net (code "45") (name "/OSCI_12M") (class "Default")
      (node (ref "C9") (pin "2") (pinfunction "2_2") (pintype "passive"))
      (node (ref "DD1") (pin "2") (pinfunction "OSCI_2") (pintype "input"))
      (node (ref "ZQ1") (pin "3") (pinfunction "3_3") (pintype "passive"))
    )
    (net (code "46") (name "/OSCO_12M") (class "Default")
      (node (ref "C6") (pin "2") (pinfunction "2_2") (pintype "passive"))
      (node (ref "DD1") (pin "3") (pinfunction "OSCO_3") (pintype "output"))
      (node (ref "ZQ1") (pin "1") (pinfunction "1_1") (pintype "passive"))
    )
    (net (code "47") (name "/POWEREN_N") (class "Default")
      (node (ref "DD1") (pin "60") (pinfunction "~{PWREN}_60") (pintype "output"))
    )
    (net (code "48") (name "/RESET_N") (class "Default")
      (node (ref "DD1") (pin "14") (pinfunction "~{RESET}_14") (pintype "input"))
      (node (ref "R6") (pin "2") (pinfunction "2_2") (pintype "passive"))
    )
    (net (code "49") (name "/SUSPEND_N") (class "Default")
      (node (ref "DD1") (pin "36") (pinfunction "~{SUSPEND}_36") (pintype "output"))
    )
    (net (code "50") (name "/USBD_N") (class "Default")
      (node (ref "FV1") (pin "1") (pinfunction "I/O1_1") (pintype "passive"))
      (node (ref "XP1") (pin "2") (pinfunction "D-_2") (pintype "passive"))
      (node (ref "XS1") (pin "A7") (pinfunction "D-_A7") (pintype "passive"))
      (node (ref "XS1") (pin "B7") (pinfunction "D-_B7") (pintype "passive"))
    )
    (net (code "51") (name "/USBD_P") (class "Default")
      (node (ref "FV1") (pin "3") (pinfunction "I/O2_3") (pintype "passive"))
      (node (ref "XP1") (pin "3") (pinfunction "D+_3") (pintype "passive"))
      (node (ref "XS1") (pin "A6") (pinfunction "D+_A6") (pintype "passive"))
      (node (ref "XS1") (pin "B6") (pinfunction "D+_B6") (pintype "passive"))
    )
    (net (code "52") (name "/USB_N") (class "Default")
      (node (ref "FV1") (pin "6") (pinfunction "I/O1_6") (pintype "passive"))
      (node (ref "R11") (pin "1") (pinfunction "1_1") (pintype "passive"))
    )
    (net (code "53") (name "/USB_P") (class "Default")
      (node (ref "FV1") (pin "4") (pinfunction "I/O2_4") (pintype "passive"))
      (node (ref "R12") (pin "1") (pinfunction "1_1") (pintype "passive"))
    )
    (net (code "54") (name "FTVCC") (class "Default")
      (node (ref "C23") (pin "2") (pinfunction "2_2") (pintype "passive"))
      (node (ref "C24") (pin "2") (pinfunction "2_2") (pintype "passive"))
      (node (ref "C25") (pin "2") (pinfunction "2_2") (pintype "passive"))
      (node (ref "C27") (pin "2") (pinfunction "2_2") (pintype "passive"))
      (node (ref "DD2") (pin "8") (pinfunction "VCCB_8") (pintype "power_in"))
      (node (ref "DD3") (pin "8") (pinfunction "VCCB_8") (pintype "power_in"))
      (node (ref "DD4") (pin "8") (pinfunction "VCCB_8") (pintype "power_in"))
      (node (ref "L4") (pin "1") (pinfunction "1_1") (pintype "passive"))
      (node (ref "R27") (pin "2") (pinfunction "2_2") (pintype "passive"))
    )
    (net (code "55") (name "GND") (class "Default")
      (node (ref "C1") (pin "1") (pinfunction "1_1") (pintype "passive"))
      (node (ref "C10") (pin "1") (pinfunction "1_1") (pintype "passive"))
      (node (ref "C11") (pin "1") (pinfunction "1_1") (pintype "passive"))
      (node (ref "C12") (pin "1") (pinfunction "1_1") (pintype "passive"))
      (node (ref "C13") (pin "1") (pinfunction "1_1") (pintype "passive"))
      (node (ref "C14") (pin "1") (pinfunction "1_1") (pintype "passive"))
      (node (ref "C15") (pin "1") (pinfunction "1_1") (pintype "passive"))
      (node (ref "C16") (pin "1") (pinfunction "1_1") (pintype "passive"))
      (node (ref "C17") (pin "1") (pinfunction "1_1") (pintype "passive"))
      (node (ref "C18") (pin "1") (pinfunction "1_1") (pintype "passive"))
      (node (ref "C19") (pin "1") (pinfunction "1_1") (pintype "passive"))
      (node (ref "C2") (pin "1") (pinfunction "1_1") (pintype "passive"))
      (node (ref "C20") (pin "1") (pinfunction "1_1") (pintype "passive"))
      (node (ref "C21") (pin "1") (pinfunction "1_1") (pintype "passive"))
      (node (ref "C22") (pin "1") (pinfunction "1_1") (pintype "passive"))
      (node (ref "C23") (pin "1") (pinfunction "1_1") (pintype "passive"))
      (node (ref "C24") (pin "1") (pinfunction "1_1") (pintype "passive"))
      (node (ref "C25") (pin "1") (pinfunction "1_1") (pintype "passive"))
      (node (ref "C26") (pin "2") (pinfunction "2_2") (pintype "passive"))
      (node (ref "C27") (pin "1") (pinfunction "1_1") (pintype "passive"))
      (node (ref "C3") (pin "1") (pinfunction "1_1") (pintype "passive"))
      (node (ref "C4") (pin "1") (pinfunction "1_1") (pintype "passive"))
      (node (ref "C5") (pin "1") (pinfunction "1_1") (pintype "passive"))
      (node (ref "C6") (pin "1") (pinfunction "1_1") (pintype "passive"))
      (node (ref "C7") (pin "1") (pinfunction "1_1") (pintype "passive"))
      (node (ref "C8") (pin "1") (pinfunction "1_1") (pintype "passive"))
      (node (ref "C9") (pin "1") (pinfunction "1_1") (pintype "passive"))
      (node (ref "DA1") (pin "2") (pinfunction "NC_2") (pintype "passive"))
      (node (ref "DA1") (pin "4") (pinfunction "GND_4") (pintype "power_in"))
      (node (ref "DA1") (pin "6") (pinfunction "NC_6") (pintype "passive"))
      (node (ref "DA1") (pin "7") (pinfunction "NC_7") (pintype "passive"))
      (node (ref "DA1") (pin "TP") (pinfunction "TP_TP") (pintype "passive"))
      (node (ref "DD1") (pin "1") (pinfunction "GND_1") (pintype "power_in"))
      (node (ref "DD1") (pin "10") (pinfunction "AGND_10") (pintype "power_in"))
      (node (ref "DD1") (pin "11") (pinfunction "GND_11") (pintype "power_in"))
      (node (ref "DD1") (pin "13") (pinfunction "TEST_13") (pintype "input"))
      (node (ref "DD1") (pin "15") (pinfunction "GND_15") (pintype "power_in"))
      (node (ref "DD1") (pin "25") (pinfunction "GND_25") (pintype "power_in"))
      (node (ref "DD1") (pin "35") (pinfunction "GND_35") (pintype "power_in"))
      (node (ref "DD1") (pin "47") (pinfunction "GND_47") (pintype "power_in"))
      (node (ref "DD1") (pin "5") (pinfunction "GND_5") (pintype "power_in"))
      (node (ref "DD1") (pin "51") (pinfunction "GND_51") (pintype "power_in"))
      (node (ref "DD2") (pin "4") (pinfunction "GND_4") (pintype "power_in"))
      (node (ref "DD3") (pin "4") (pinfunction "GND_4") (pintype "power_in"))
      (node (ref "DD4") (pin "4") (pinfunction "GND_4") (pintype "power_in"))
      (node (ref "DD4") (pin "5") (pinfunction "DIR_5") (pintype "input"))
      (node (ref "DD5") (pin "2") (pinfunction "GND_2") (pintype "power_in"))
      (node (ref "FV1") (pin "2") (pinfunction "GND_2") (pintype "passive"))
      (node (ref "R1") (pin "1") (pinfunction "1_1") (pintype "passive"))
      (node (ref "R10") (pin "1") (pinfunction "1_1") (pintype "passive"))
      (node (ref "R19") (pin "2") (pinfunction "2_2") (pintype "passive"))
      (node (ref "R2") (pin "1") (pinfunction "1_1") (pintype "passive"))
      (node (ref "R7") (pin "1") (pinfunction "1_1") (pintype "passive"))
      (node (ref "R9") (pin "2") (pinfunction "2_2") (pintype "passive"))
      (node (ref "VT1") (pin "2") (pinfunction "S_2") (pintype "passive"))
      (node (ref "XP1") (pin "4") (pinfunction "GND_4") (pintype "passive"))
      (node (ref "XP2") (pin "10") (pintype "passive"))
      (node (ref "XP2") (pin "2") (pintype "passive"))
      (node (ref "XS1") (pin "A1") (pinfunction "GND_A1") (pintype "passive"))
      (node (ref "XS1") (pin "A12") (pinfunction "GND_A12") (pintype "passive"))
      (node (ref "XS1") (pin "B1") (pinfunction "GND_B1") (pintype "passive"))
      (node (ref "XS1") (pin "B12") (pinfunction "GND_B12") (pintype "passive"))
      (node (ref "XS2") (pin "3") (pintype "passive"))
      (node (ref "XS2") (pin "5") (pintype "passive"))
      (node (ref "XS2") (pin "9") (pintype "passive"))
      (node (ref "XS3") (pin "2") (pintype "passive"))
      (node (ref "XS3") (pin "5") (pintype "passive"))
    )
    (net (code "56") (name "Net-(DA1-FB)") (class "Default")
      (node (ref "DA1") (pin "3") (pinfunction "FB_3") (pintype "input"))
      (node (ref "R7") (pin "2") (pinfunction "2_2") (pintype "passive"))
      (node (ref "R8") (pin "1") (pinfunction "1_1") (pintype "passive"))
    )
    (net (code "57") (name "Net-(DD1-DM)") (class "Default")
      (node (ref "DD1") (pin "7") (pinfunction "DM_7") (pintype "bidirectional"))
      (node (ref "R11") (pin "2") (pinfunction "2_2") (pintype "passive"))
    )
    (net (code "58") (name "Net-(DD1-DP)") (class "Default")
      (node (ref "DD1") (pin "8") (pinfunction "DP_8") (pintype "bidirectional"))
      (node (ref "R12") (pin "2") (pinfunction "2_2") (pintype "passive"))
    )
    (net (code "59") (name "Net-(DD1-REF)") (class "Default")
      (node (ref "DD1") (pin "6") (pinfunction "REF_6") (pintype "passive"))
      (node (ref "R10") (pin "2") (pinfunction "2_2") (pintype "passive"))
    )
    (net (code "60") (name "Net-(DD2-B1)") (class "Default")
      (node (ref "DD2") (pin "7") (pinfunction "B1_7") (pintype "bidirectional"))
      (node (ref "R21") (pin "1") (pinfunction "1_1") (pintype "passive"))
    )
    (net (code "61") (name "Net-(DD2-B2)") (class "Default")
      (node (ref "DD2") (pin "6") (pinfunction "B2_6") (pintype "bidirectional"))
      (node (ref "R22") (pin "1") (pinfunction "1_1") (pintype "passive"))
    )
    (net (code "62") (name "Net-(DD3-B1)") (class "Default")
      (node (ref "DD3") (pin "7") (pinfunction "B1_7") (pintype "bidirectional"))
      (node (ref "R23") (pin "1") (pinfunction "1_1") (pintype "passive"))
    )
    (net (code "63") (name "Net-(DD3-B2)") (class "Default")
      (node (ref "DD3") (pin "6") (pinfunction "B2_6") (pintype "bidirectional"))
      (node (ref "R24") (pin "1") (pinfunction "1_1") (pintype "passive"))
    )
    (net (code "64") (name "Net-(DD4-A1)") (class "Default")
      (node (ref "DD4") (pin "2") (pinfunction "A1_2") (pintype "bidirectional"))
      (node (ref "R14") (pin "2") (pinfunction "2_2") (pintype "passive"))
    )
    (net (code "65") (name "Net-(DD4-A2)") (class "Default")
      (node (ref "DD4") (pin "3") (pinfunction "A2_3") (pintype "bidirectional"))
      (node (ref "R15") (pin "2") (pinfunction "2_2") (pintype "passive"))
    )
    (net (code "66") (name "Net-(DD4-B1)") (class "Default")
      (node (ref "DD4") (pin "7") (pinfunction "B1_7") (pintype "bidirectional"))
      (node (ref "R25") (pin "1") (pinfunction "1_1") (pintype "passive"))
    )
    (net (code "67") (name "Net-(DD4-B2)") (class "Default")
      (node (ref "DD4") (pin "6") (pinfunction "B2_6") (pintype "bidirectional"))
      (node (ref "R26") (pin "1") (pinfunction "1_1") (pintype "passive"))
    )
    (net (code "68") (name "Net-(DD5-DO)") (class "Default")
      (node (ref "DD5") (pin "1") (pinfunction "DO_1") (pintype "output"))
      (node (ref "R20") (pin "2") (pinfunction "2_2") (pintype "passive"))
    )
    (net (code "69") (name "Net-(HL1-К)") (class "Default")
      (node (ref "HL1") (pin "2") (pinfunction "К_2") (pintype "passive"))
      (node (ref "R3") (pin "1") (pinfunction "1_1") (pintype "passive"))
    )
    (net (code "70") (name "Net-(HL2-К)") (class "Default")
      (node (ref "HL2") (pin "2") (pinfunction "К_2") (pintype "passive"))
      (node (ref "R4") (pin "1") (pinfunction "1_1") (pintype "passive"))
    )
    (net (code "71") (name "Net-(HL3-К)") (class "Default")
      (node (ref "HL3") (pin "2") (pinfunction "К_2") (pintype "passive"))
      (node (ref "R5") (pin "1") (pinfunction "1_1") (pintype "passive"))
    )
    (net (code "72") (name "Net-(VT1-D)") (class "Default")
      (node (ref "R27") (pin "1") (pinfunction "1_1") (pintype "passive"))
      (node (ref "R28") (pin "1") (pinfunction "1_1") (pintype "passive"))
      (node (ref "R29") (pin "1") (pinfunction "1_1") (pintype "passive"))
      (node (ref "R30") (pin "1") (pinfunction "1_1") (pintype "passive"))
      (node (ref "VT1") (pin "3") (pinfunction "D_3") (pintype "passive"))
    )
    (net (code "73") (name "Net-(VT1-G)") (class "Default")
      (node (ref "R16") (pin "2") (pinfunction "2_2") (pintype "passive"))
      (node (ref "R19") (pin "1") (pinfunction "1_1") (pintype "passive"))
      (node (ref "VT1") (pin "1") (pinfunction "G_1") (pintype "passive"))
    )
    (net (code "74") (name "Net-(XS1-CC1)") (class "Default")
      (node (ref "R2") (pin "2") (pinfunction "2_2") (pintype "passive"))
      (node (ref "XS1") (pin "A5") (pinfunction "CC1_A5") (pintype "passive"))
    )
    (net (code "75") (name "Net-(XS1-CC2)") (class "Default")
      (node (ref "R1") (pin "2") (pinfunction "2_2") (pintype "passive"))
      (node (ref "XS1") (pin "B5") (pinfunction "CC2_B5") (pintype "passive"))
    )
    (net (code "76") (name "SHLD") (class "Default")
      (node (ref "C3") (pin "2") (pinfunction "2_2") (pintype "passive"))
      (node (ref "R9") (pin "1") (pinfunction "1_1") (pintype "passive"))
      (node (ref "XP1") (pin "SH") (pinfunction "КОРПУС_SH") (pintype "passive"))
      (node (ref "XS1") (pin "SH") (pinfunction "КОРПУС_SH") (pintype "passive"))
    )
    (net (code "77") (name "TVCC") (class "Default")
      (node (ref "L4") (pin "2") (pinfunction "2_2") (pintype "passive"))
      (node (ref "XP2") (pin "4") (pintype "passive"))
      (node (ref "XS2") (pin "1") (pintype "passive"))
      (node (ref "XS3") (pin "1") (pintype "passive"))
    )
    (net (code "78") (name "VBUS") (class "Default")
      (node (ref "L1") (pin "1") (pinfunction "1_1") (pintype "passive"))
      (node (ref "XP1") (pin "1") (pinfunction "VBUS_1") (pintype "passive"))
      (node (ref "XS1") (pin "A4") (pinfunction "VBUS_A4") (pintype "passive"))
      (node (ref "XS1") (pin "A9") (pinfunction "VBUS_A9") (pintype "passive"))
      (node (ref "XS1") (pin "B4") (pinfunction "VBUS_B4") (pintype "passive"))
      (node (ref "XS1") (pin "B9") (pinfunction "VBUS_B9") (pintype "passive"))
    )
    (net (code "79") (name "VCC1P8") (class "Default")
      (node (ref "C16") (pin "2") (pinfunction "2_2") (pintype "passive"))
      (node (ref "C17") (pin "2") (pinfunction "2_2") (pintype "passive"))
      (node (ref "C18") (pin "2") (pinfunction "2_2") (pintype "passive"))
      (node (ref "C19") (pin "2") (pinfunction "2_2") (pintype "passive"))
      (node (ref "DD1") (pin "12") (pinfunction "VCORE_12") (pintype "power_in"))
      (node (ref "DD1") (pin "37") (pinfunction "VCORE_37") (pintype "power_in"))
      (node (ref "DD1") (pin "49") (pinfunction "VREGOUT_49") (pintype "power_in"))
      (node (ref "DD1") (pin "64") (pinfunction "VCORE_64") (pintype "power_in"))
    )
    (net (code "80") (name "VCC3P3") (class "Default")
      (node (ref "C12") (pin "2") (pinfunction "2_2") (pintype "passive"))
      (node (ref "C13") (pin "2") (pinfunction "2_2") (pintype "passive"))
      (node (ref "C14") (pin "2") (pinfunction "2_2") (pintype "passive"))
      (node (ref "C15") (pin "2") (pinfunction "2_2") (pintype "passive"))
      (node (ref "C20") (pin "2") (pinfunction "2_2") (pintype "passive"))
      (node (ref "C21") (pin "2") (pinfunction "2_2") (pintype "passive"))
      (node (ref "C22") (pin "2") (pinfunction "2_2") (pintype "passive"))
      (node (ref "C26") (pin "1") (pinfunction "1_1") (pintype "passive"))
      (node (ref "C4") (pin "2") (pinfunction "2_2") (pintype "passive"))
      (node (ref "C5") (pin "2") (pinfunction "2_2") (pintype "passive"))
      (node (ref "DA1") (pin "1") (pinfunction "OUT_1") (pintype "power_in"))
      (node (ref "DD1") (pin "20") (pinfunction "VCCIO_20") (pintype "power_in"))
      (node (ref "DD1") (pin "31") (pinfunction "VCCIO_31") (pintype "power_in"))
      (node (ref "DD1") (pin "42") (pinfunction "VCCIO_42") (pintype "power_in"))
      (node (ref "DD1") (pin "50") (pinfunction "VREGIN_50") (pintype "power_in"))
      (node (ref "DD1") (pin "56") (pinfunction "VCCIO_56") (pintype "power_in"))
      (node (ref "DD2") (pin "1") (pinfunction "VCCA_1") (pintype "power_in"))
      (node (ref "DD2") (pin "5") (pinfunction "DIR_5") (pintype "input"))
      (node (ref "DD3") (pin "1") (pinfunction "VCCA_1") (pintype "power_in"))
      (node (ref "DD3") (pin "5") (pinfunction "DIR_5") (pintype "input"))
      (node (ref "DD4") (pin "1") (pinfunction "VCCA_1") (pintype "power_in"))
      (node (ref "DD5") (pin "6") (pinfunction "VCC_6") (pintype "power_in"))
      (node (ref "HL1") (pin "1") (pinfunction "А_1") (pintype "passive"))
      (node (ref "HL2") (pin "1") (pinfunction "А_1") (pintype "passive"))
      (node (ref "HL3") (pin "1") (pinfunction "А_1") (pintype "passive"))
      (node (ref "L2") (pin "1") (pinfunction "1_1") (pintype "passive"))
      (node (ref "L3") (pin "1") (pinfunction "1_1") (pintype "passive"))
      (node (ref "R13") (pin "2") (pinfunction "2_2") (pintype "passive"))
      (node (ref "R17") (pin "2") (pinfunction "2_2") (pintype "passive"))
      (node (ref "R18") (pin "2") (pinfunction "2_2") (pintype "passive"))
      (node (ref "R6") (pin "1") (pinfunction "1_1") (pintype "passive"))
      (node (ref "R8") (pin "2") (pinfunction "2_2") (pintype "passive"))
    )
    (net (code "81") (name "VCC5P0") (class "Default")
      (node (ref "C1") (pin "2") (pinfunction "2_2") (pintype "passive"))
      (node (ref "C2") (pin "2") (pinfunction "2_2") (pintype "passive"))
      (node (ref "DA1") (pin "5") (pinfunction "EN_5") (pintype "input"))
      (node (ref "DA1") (pin "8") (pinfunction "IN_8") (pintype "power_in"))
      (node (ref "FV1") (pin "5") (pinfunction "VBUS_5") (pintype "passive"))
      (node (ref "L1") (pin "2") (pinfunction "2_2") (pintype "passive"))
    )
    (net (code "82") (name "VCC_PHY") (class "Default")
      (node (ref "C10") (pin "2") (pinfunction "2_2") (pintype "passive"))
      (node (ref "C7") (pin "2") (pinfunction "2_2") (pintype "passive"))
      (node (ref "DD1") (pin "4") (pinfunction "VPHY_4") (pintype "power_in"))
      (node (ref "L2") (pin "2") (pinfunction "2_2") (pintype "passive"))
    )
    (net (code "83") (name "VCC_PLL") (class "Default")
      (node (ref "C11") (pin "2") (pinfunction "2_2") (pintype "passive"))
      (node (ref "C8") (pin "2") (pinfunction "2_2") (pintype "passive"))
      (node (ref "DD1") (pin "9") (pinfunction "VPLL_9") (pintype "power_in"))
      (node (ref "L3") (pin "2") (pinfunction "2_2") (pintype "passive"))
    )
    (net (code "84") (name "unconnected-(XP2-Pad7)") (class "Default")
      (node (ref "XP2") (pin "7") (pintype "passive+no_connect"))
    )
    (net (code "85") (name "unconnected-(XS1-SBU1-PadA8)") (class "Default")
      (node (ref "XS1") (pin "A8") (pinfunction "SBU1_A8") (pintype "passive+no_connect"))
    )
    (net (code "86") (name "unconnected-(XS1-SBU2-PadB8)") (class "Default")
      (node (ref "XS1") (pin "B8") (pinfunction "SBU2_B8") (pintype "passive+no_connect"))
    )
    (net (code "87") (name "unconnected-(XS2-Pad7)") (class "Default")
      (node (ref "XS2") (pin "7") (pintype "passive+no_connect"))
    )
    (net (code "88") (name "unconnected-(XS3-Pad6)") (class "Default")
      (node (ref "XS3") (pin "6") (pintype "passive+no_connect"))
    )
  )
)
